# usb_ir.net
KiCad netlist of a schematic drawn in Altium Designer
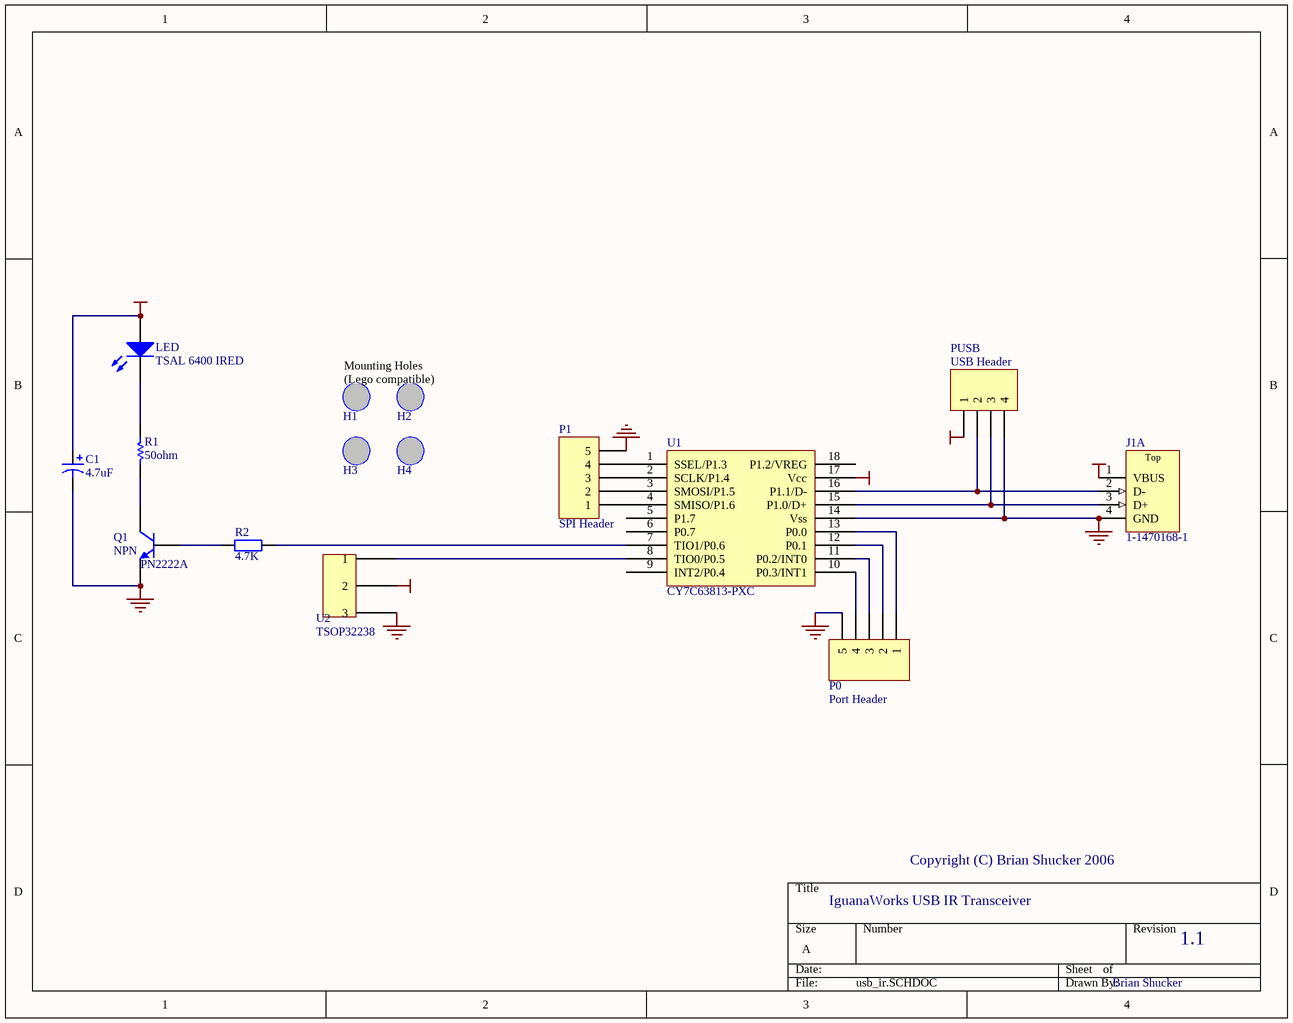
[diagram p0: usb_ir.SCHDOC]

(export (version "E")
  (design (tool "Eeschema 10.0.6"))
  (components
    (comp (ref "C1")
      (value "4.7uF")
      (footprint "CAPPR2-5x6.8")
      (description "Polarized Capacitor (Radial)")
      (fields (field (name "Comment") "Cap Pol1") (field (name "PUBLISHER") "Altium Limited"))
      (libsource (lib "Miscellaneous Devices") (part "Cap Pol1"))
    )
    (comp (ref "H1")
      (value "Lego Hole")
      (footprint "Lego Hole")
      (description "Standard lego-size mounting hole")
      (libsource (lib "robo") (part "Lego Hole"))
    )
    (comp (ref "H2")
      (value "Lego Hole")
      (footprint "Lego Hole")
      (description "Standard lego-size mounting hole")
      (libsource (lib "robo") (part "Lego Hole"))
    )
    (comp (ref "H3")
      (value "Lego Hole")
      (footprint "Lego Hole")
      (description "Standard lego-size mounting hole")
      (libsource (lib "robo") (part "Lego Hole"))
    )
    (comp (ref "H4")
      (value "Lego Hole")
      (footprint "Lego Hole")
      (description "Standard lego-size mounting hole")
      (libsource (lib "robo") (part "Lego Hole"))
    )
    (comp (ref "J1")
      (value "1-1470168-1")
      (footprint "1470695A")
      (description "USB 1.1, Right Angle, Thru-Hole, A Type, Receptacle, 4x4 Position, Stacked, Black")
      (fields (field (name "PUBLISHER") "Altium Limited"))
      (libsource (lib "AMP Serial Bus USB") (part "1-1470168-1"))
    )
    (comp (ref "LED")
      (value "TSAL 6400 IRED")
      (footprint "LED")
      (description "Typical INFRARED GaAs LED")
      (fields (field (name "PUBLISHER") "Altium Limited"))
      (libsource (lib "Miscellaneous Devices") (part "LED0"))
    )
    (comp (ref "P0")
      (value "Port Header")
      (footprint "HDR1X5")
      (description "Header, 5-Pin")
      (fields (field (name "PUBLISHER") "Altium Limited"))
      (libsource (lib "Miscellaneous Connectors") (part "Header 5"))
    )
    (comp (ref "P1")
      (value "SPI Header")
      (footprint "HDR1X5")
      (description "Header, 5-Pin")
      (fields (field (name "PUBLISHER") "Altium Limited"))
      (libsource (lib "") (part "Header 5_1"))
    )
    (comp (ref "PUSB")
      (value "USB Header")
      (footprint "HDR1X4")
      (description "Header, 4-Pin")
      (fields (field (name "PUBLISHER") "Altium Limited"))
      (libsource (lib "Miscellaneous Connectors") (part "Header 4"))
    )
    (comp (ref "Q1")
      (value "NPN")
      (footprint "TO-92")
      (description "NPN Bipolar Transistor")
      (fields (field (name "PUBLISHER") "Altium Limited"))
      (libsource (lib "Miscellaneous Devices") (part "NPN"))
    )
    (comp (ref "R1")
      (value "50ohm")
      (footprint "AXIAL-0.4")
      (description "Semiconductor Resistor")
      (fields (field (name "PUBLISHER") "Altium Limited"))
      (libsource (lib "Miscellaneous Devices") (part "Res Semi"))
    )
    (comp (ref "R2")
      (value "4.7K")
      (footprint "AXIAL-0.4")
      (description "Resistor")
      (fields (field (name "Comment") "Res2") (field (name "PUBLISHER") "Altium Limited"))
      (libsource (lib "Miscellaneous Devices") (part "Res2"))
    )
    (comp (ref "U1")
      (value "CY7C63813-PXC")
      (footprint "DIP-18")
      (description "USB microcontroller")
      (libsource (lib "ir") (part "CY7C63813-PXC"))
    )
    (comp (ref "U2")
      (value "TSOP32238")
      (footprint "vishay1")
      (libsource (lib "ir") (part "TSOP2238 IR RECEIVER MODULE"))
    )
  )
  (nets
    (net (code "1") (name "GND") (class "Default")
      (node (ref "C1") (pin "2") (pinfunction "2_2") (pintype "passive"))
      (node (ref "J1") (pin "4") (pinfunction "GND_4") (pintype "power_in"))
      (node (ref "P0") (pin "5") (pinfunction "5_5") (pintype "passive"))
      (node (ref "P1") (pin "5") (pinfunction "5_5") (pintype "passive"))
      (node (ref "PUSB") (pin "4") (pinfunction "4_4") (pintype "passive"))
      (node (ref "Q1") (pin "3") (pinfunction "E_3") (pintype "passive"))
      (node (ref "U1") (pin "14") (pinfunction "Vss_14") (pintype "passive"))
      (node (ref "U2") (pin "3") (pinfunction "3_3") (pintype "passive"))
    )
    (net (code "2") (name "Net-(J1A-D+)") (class "Default")
      (node (ref "J1") (pin "3") (pinfunction "D+_3") (pintype "input"))
      (node (ref "PUSB") (pin "3") (pinfunction "3_3") (pintype "passive"))
      (node (ref "U1") (pin "15") (pinfunction "P1.0/D+_15") (pintype "passive"))
    )
    (net (code "3") (name "Net-(J1A-D-)") (class "Default")
      (node (ref "J1") (pin "2") (pinfunction "D-_2") (pintype "input"))
      (node (ref "PUSB") (pin "2") (pinfunction "2_2") (pintype "passive"))
      (node (ref "U1") (pin "16") (pinfunction "P1.1/D-_16") (pintype "passive"))
    )
    (net (code "4") (name "Net-(LED-K)") (class "Default")
      (node (ref "LED") (pin "2") (pinfunction "K_2") (pintype "passive"))
      (node (ref "R1") (pin "2") (pinfunction "2_2") (pintype "passive"))
    )
    (net (code "5") (name "Net-(Q1-B)") (class "Default")
      (node (ref "Q1") (pin "2") (pinfunction "B_2") (pintype "passive"))
      (node (ref "R2") (pin "2") (pinfunction "2_2") (pintype "passive"))
    )
    (net (code "6") (name "Net-(Q1-C)") (class "Default")
      (node (ref "Q1") (pin "1") (pinfunction "C_1") (pintype "passive"))
      (node (ref "R1") (pin "1") (pinfunction "1_1") (pintype "passive"))
    )
    (net (code "7") (name "Net-(U1-P0.0)") (class "Default")
      (node (ref "P0") (pin "1") (pinfunction "1_1") (pintype "passive"))
      (node (ref "U1") (pin "13") (pinfunction "P0.0_13") (pintype "passive"))
    )
    (net (code "8") (name "Net-(U1-P0.1)") (class "Default")
      (node (ref "P0") (pin "2") (pinfunction "2_2") (pintype "passive"))
      (node (ref "U1") (pin "12") (pinfunction "P0.1_12") (pintype "passive"))
    )
    (net (code "9") (name "Net-(U1-P0.2{slash}INT0)") (class "Default")
      (node (ref "P0") (pin "3") (pinfunction "3_3") (pintype "passive"))
      (node (ref "U1") (pin "11") (pinfunction "P0.2/INT0_11") (pintype "passive"))
    )
    (net (code "10") (name "Net-(U1-P0.3{slash}INT1)") (class "Default")
      (node (ref "P0") (pin "4") (pinfunction "4_4") (pintype "passive"))
      (node (ref "U1") (pin "10") (pinfunction "P0.3/INT1_10") (pintype "passive"))
    )
    (net (code "11") (name "Net-(U1-SCLK{slash}P1.4)") (class "Default")
      (node (ref "P1") (pin "3") (pinfunction "3_3") (pintype "passive"))
      (node (ref "U1") (pin "2") (pinfunction "SCLK/P1.4_2") (pintype "passive"))
    )
    (net (code "12") (name "Net-(U1-SMISO{slash}P1.6)") (class "Default")
      (node (ref "P1") (pin "1") (pinfunction "1_1") (pintype "passive"))
      (node (ref "U1") (pin "4") (pinfunction "SMISO/P1.6_4") (pintype "passive"))
    )
    (net (code "13") (name "Net-(U1-SMOSI{slash}P1.5)") (class "Default")
      (node (ref "P1") (pin "2") (pinfunction "2_2") (pintype "passive"))
      (node (ref "U1") (pin "3") (pinfunction "SMOSI/P1.5_3") (pintype "passive"))
    )
    (net (code "14") (name "Net-(U1-SSEL{slash}P1.3)") (class "Default")
      (node (ref "P1") (pin "4") (pinfunction "4_4") (pintype "passive"))
      (node (ref "U1") (pin "1") (pinfunction "SSEL/P1.3_1") (pintype "passive"))
    )
    (net (code "15") (name "Net-(U1-TIO0{slash}P0.5)") (class "Default")
      (node (ref "U1") (pin "8") (pinfunction "TIO0/P0.5_8") (pintype "passive"))
      (node (ref "U2") (pin "1") (pinfunction "1_1") (pintype "open_collector"))
    )
    (net (code "16") (name "Net-(U1-TIO1{slash}P0.6)") (class "Default")
      (node (ref "R2") (pin "1") (pinfunction "1_1") (pintype "passive"))
      (node (ref "U1") (pin "7") (pinfunction "TIO1/P0.6_7") (pintype "passive"))
    )
    (net (code "17") (name "VCC") (class "Default")
      (node (ref "C1") (pin "1") (pinfunction "1_1") (pintype "passive"))
      (node (ref "J1") (pin "1") (pinfunction "VBUS_1") (pintype "power_in"))
      (node (ref "LED") (pin "1") (pinfunction "A_1") (pintype "passive"))
      (node (ref "PUSB") (pin "1") (pinfunction "1_1") (pintype "passive"))
      (node (ref "U1") (pin "17") (pinfunction "Vcc_17") (pintype "passive"))
      (node (ref "U2") (pin "2") (pinfunction "2_2") (pintype "power_in"))
    )
    (net (code "18") (name "unconnected-(U1-INT2{slash}P0.4-Pad9)") (class "Default")
      (node (ref "U1") (pin "9") (pinfunction "INT2/P0.4_9") (pintype "passive"))
    )
    (net (code "19") (name "unconnected-(U1-P0.7-Pad6)") (class "Default")
      (node (ref "U1") (pin "6") (pinfunction "P0.7_6") (pintype "passive"))
    )
    (net (code "20") (name "unconnected-(U1-P1.2{slash}VREG-Pad18)") (class "Default")
      (node (ref "U1") (pin "18") (pinfunction "P1.2/VREG_18") (pintype "passive"))
    )
    (net (code "21") (name "unconnected-(U1-P1.7-Pad5)") (class "Default")
      (node (ref "U1") (pin "5") (pinfunction "P1.7_5") (pintype "passive"))
    )
  )
)
